# Connector.net
KiCad netlist of a schematic drawn in Altium Designer
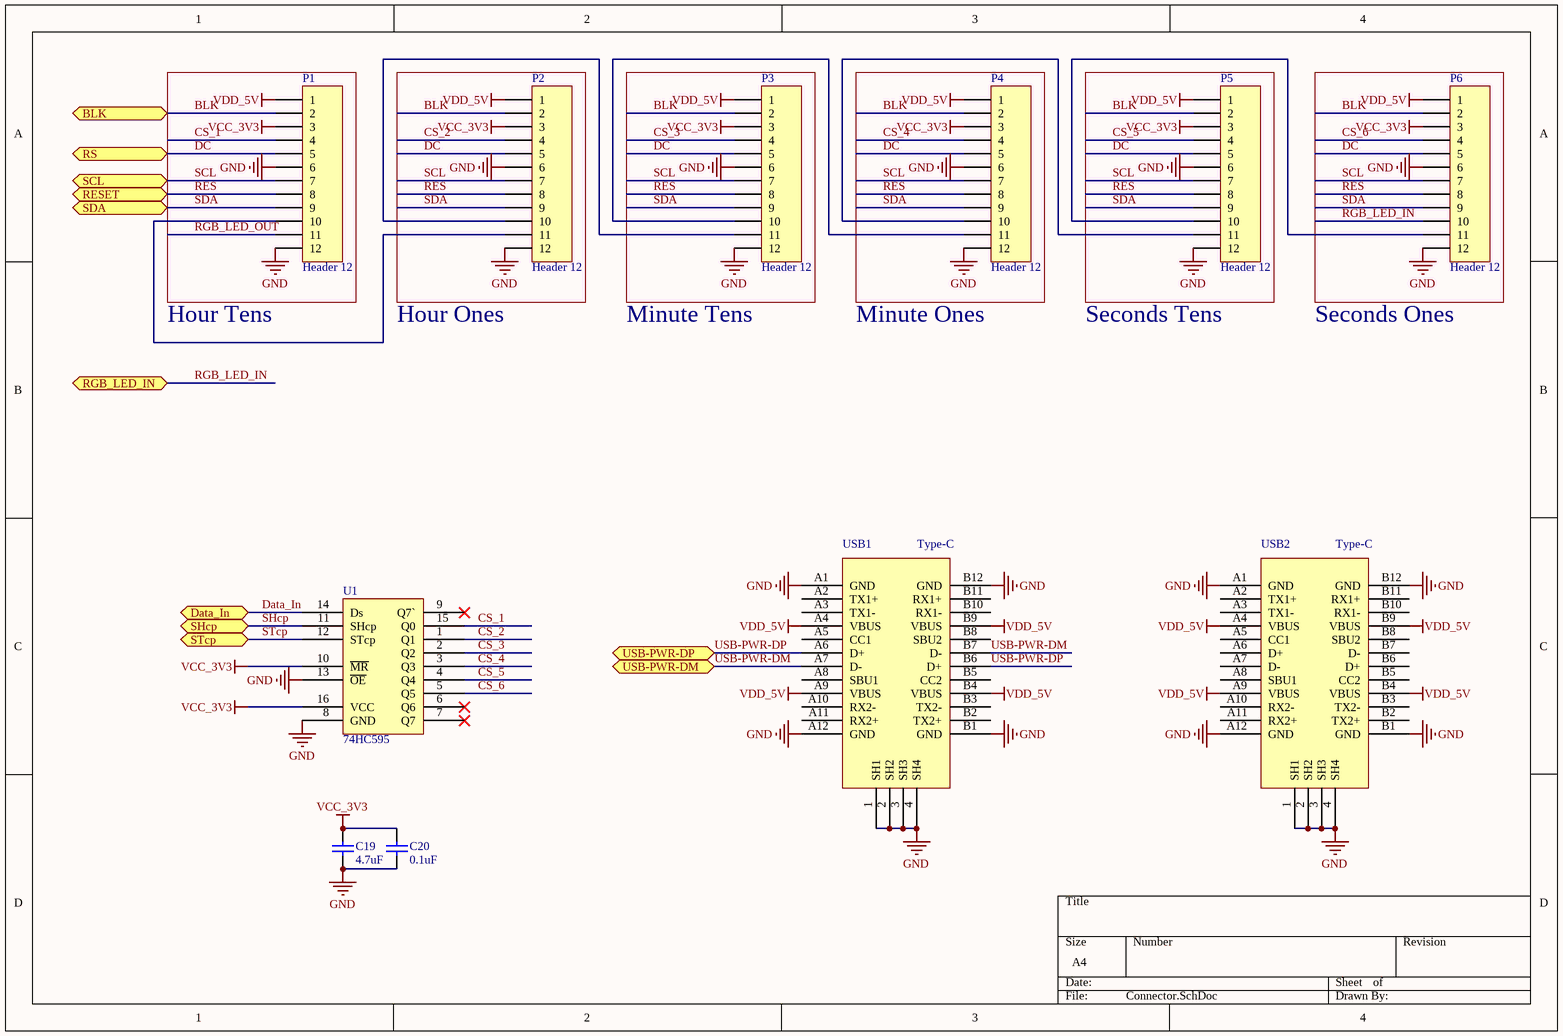
[diagram p0: Connector.SchDoc]

(export (version "E")
  (design (tool "Eeschema 10.0.6"))
  (components
    (comp (ref "C19")
      (value "4.7uF")
      (footprint "C0603")
      (description "Capacitor")
      (fields (field (name "PUBLISHER") "Altium Limited"))
      (libsource (lib "basic") (part "Cap"))
    )
    (comp (ref "C20")
      (value "0.1uF")
      (footprint "C0603")
      (description "Capacitor")
      (fields (field (name "PUBLISHER") "Altium Limited"))
      (libsource (lib "basic") (part "Cap"))
    )
    (comp (ref "P1")
      (value "Header 12")
      (footprint "SIP12-1.27")
      (description "Header, 12-Pin")
      (fields (field (name "PUBLISHER") "Altium Limited"))
      (libsource (lib "Miscellaneous Connectors") (part "Header 12"))
    )
    (comp (ref "P2")
      (value "Header 12")
      (footprint "SIP12-1.27")
      (description "Header, 12-Pin")
      (fields (field (name "PUBLISHER") "Altium Limited"))
      (libsource (lib "Miscellaneous Connectors") (part "Header 12"))
    )
    (comp (ref "P3")
      (value "Header 12")
      (footprint "SIP12-1.27")
      (description "Header, 12-Pin")
      (fields (field (name "PUBLISHER") "Altium Limited"))
      (libsource (lib "Miscellaneous Connectors") (part "Header 12"))
    )
    (comp (ref "P4")
      (value "Header 12")
      (footprint "SIP12-1.27")
      (description "Header, 12-Pin")
      (fields (field (name "PUBLISHER") "Altium Limited"))
      (libsource (lib "Miscellaneous Connectors") (part "Header 12"))
    )
    (comp (ref "P5")
      (value "Header 12")
      (footprint "SIP12-1.27")
      (description "Header, 12-Pin")
      (fields (field (name "PUBLISHER") "Altium Limited"))
      (libsource (lib "Miscellaneous Connectors") (part "Header 12"))
    )
    (comp (ref "P6")
      (value "Header 12")
      (footprint "SIP12-1.27")
      (description "Header, 12-Pin")
      (fields (field (name "PUBLISHER") "Altium Limited"))
      (libsource (lib "Miscellaneous Connectors") (part "Header 12"))
    )
    (comp (ref "U1")
      (value "74HC595")
      (footprint "SO-16_L")
      (libsource (lib "20210909_EleksTube_IPS") (part "74HC595"))
    )
    (comp (ref "USB1")
      (value "Type-C")
      (footprint "Type-C-TOP")
      (libsource (lib "MyPcbLib") (part "USB-Type-C-TOP"))
    )
    (comp (ref "USB2")
      (value "Type-C")
      (footprint "Type-C-TOP")
      (libsource (lib "MyPcbLib") (part "USB-Type-C-TOP"))
    )
  )
  (nets
    (net (code "1") (name "/BLK") (class "Default")
      (node (ref "P1") (pin "2") (pinfunction "2_2") (pintype "passive"))
      (node (ref "P2") (pin "2") (pinfunction "2_2") (pintype "passive"))
      (node (ref "P3") (pin "2") (pinfunction "2_2") (pintype "passive"))
      (node (ref "P4") (pin "2") (pinfunction "2_2") (pintype "passive"))
      (node (ref "P5") (pin "2") (pinfunction "2_2") (pintype "passive"))
      (node (ref "P6") (pin "2") (pinfunction "2_2") (pintype "passive"))
    )
    (net (code "2") (name "/CS_1") (class "Default")
      (node (ref "P1") (pin "4") (pinfunction "4_4") (pintype "passive"))
      (node (ref "U1") (pin "15") (pinfunction "Q0_15") (pintype "passive"))
    )
    (net (code "3") (name "/CS_2") (class "Default")
      (node (ref "P2") (pin "4") (pinfunction "4_4") (pintype "passive"))
      (node (ref "U1") (pin "1") (pinfunction "Q1_1") (pintype "passive"))
    )
    (net (code "4") (name "/CS_3") (class "Default")
      (node (ref "P3") (pin "4") (pinfunction "4_4") (pintype "passive"))
      (node (ref "U1") (pin "2") (pinfunction "Q2_2") (pintype "passive"))
    )
    (net (code "5") (name "/CS_4") (class "Default")
      (node (ref "P4") (pin "4") (pinfunction "4_4") (pintype "passive"))
      (node (ref "U1") (pin "3") (pinfunction "Q3_3") (pintype "passive"))
    )
    (net (code "6") (name "/CS_5") (class "Default")
      (node (ref "P5") (pin "4") (pinfunction "4_4") (pintype "passive"))
      (node (ref "U1") (pin "4") (pinfunction "Q4_4") (pintype "passive"))
    )
    (net (code "7") (name "/CS_6") (class "Default")
      (node (ref "P6") (pin "4") (pinfunction "4_4") (pintype "passive"))
      (node (ref "U1") (pin "5") (pinfunction "Q5_5") (pintype "passive"))
    )
    (net (code "8") (name "/DC") (class "Default")
      (node (ref "P1") (pin "5") (pinfunction "5_5") (pintype "passive"))
      (node (ref "P2") (pin "5") (pinfunction "5_5") (pintype "passive"))
      (node (ref "P3") (pin "5") (pinfunction "5_5") (pintype "passive"))
      (node (ref "P4") (pin "5") (pinfunction "5_5") (pintype "passive"))
      (node (ref "P5") (pin "5") (pinfunction "5_5") (pintype "passive"))
      (node (ref "P6") (pin "5") (pinfunction "5_5") (pintype "passive"))
    )
    (net (code "9") (name "/Data_In") (class "Default")
      (node (ref "U1") (pin "14") (pinfunction "Ds_14") (pintype "passive"))
    )
    (net (code "10") (name "/RES") (class "Default")
      (node (ref "P1") (pin "8") (pinfunction "8_8") (pintype "passive"))
      (node (ref "P2") (pin "8") (pinfunction "8_8") (pintype "passive"))
      (node (ref "P3") (pin "8") (pinfunction "8_8") (pintype "passive"))
      (node (ref "P4") (pin "8") (pinfunction "8_8") (pintype "passive"))
      (node (ref "P5") (pin "8") (pinfunction "8_8") (pintype "passive"))
      (node (ref "P6") (pin "8") (pinfunction "8_8") (pintype "passive"))
    )
    (net (code "11") (name "/RGB_LED_IN") (class "Default")
      (node (ref "P6") (pin "10") (pinfunction "10_10") (pintype "passive"))
    )
    (net (code "12") (name "/RGB_LED_OUT") (class "Default")
      (node (ref "P1") (pin "11") (pinfunction "11_11") (pintype "passive"))
    )
    (net (code "13") (name "/SCL") (class "Default")
      (node (ref "P1") (pin "7") (pinfunction "7_7") (pintype "passive"))
      (node (ref "P2") (pin "7") (pinfunction "7_7") (pintype "passive"))
      (node (ref "P3") (pin "7") (pinfunction "7_7") (pintype "passive"))
      (node (ref "P4") (pin "7") (pinfunction "7_7") (pintype "passive"))
      (node (ref "P5") (pin "7") (pinfunction "7_7") (pintype "passive"))
      (node (ref "P6") (pin "7") (pinfunction "7_7") (pintype "passive"))
    )
    (net (code "14") (name "/SDA") (class "Default")
      (node (ref "P1") (pin "9") (pinfunction "9_9") (pintype "passive"))
      (node (ref "P2") (pin "9") (pinfunction "9_9") (pintype "passive"))
      (node (ref "P3") (pin "9") (pinfunction "9_9") (pintype "passive"))
      (node (ref "P4") (pin "9") (pinfunction "9_9") (pintype "passive"))
      (node (ref "P5") (pin "9") (pinfunction "9_9") (pintype "passive"))
      (node (ref "P6") (pin "9") (pinfunction "9_9") (pintype "passive"))
    )
    (net (code "15") (name "/SHcp") (class "Default")
      (node (ref "U1") (pin "11") (pinfunction "SHcp_11") (pintype "passive"))
    )
    (net (code "16") (name "/STcp") (class "Default")
      (node (ref "U1") (pin "12") (pinfunction "STcp_12") (pintype "passive"))
    )
    (net (code "17") (name "/USB-PWR-DM") (class "Default")
      (node (ref "USB1") (pin "A7") (pinfunction "D-_A7") (pintype "passive"))
      (node (ref "USB1") (pin "B7") (pinfunction "D-_B7") (pintype "passive"))
    )
    (net (code "18") (name "/USB-PWR-DP") (class "Default")
      (node (ref "USB1") (pin "A6") (pinfunction "D+_A6") (pintype "passive"))
      (node (ref "USB1") (pin "B6") (pinfunction "D+_B6") (pintype "passive"))
    )
    (net (code "19") (name "GND") (class "Default")
      (node (ref "C19") (pin "2") (pinfunction "2_2") (pintype "passive"))
      (node (ref "C20") (pin "2") (pinfunction "2_2") (pintype "passive"))
      (node (ref "P1") (pin "12") (pinfunction "12_12") (pintype "passive"))
      (node (ref "P1") (pin "6") (pinfunction "6_6") (pintype "passive"))
      (node (ref "P2") (pin "12") (pinfunction "12_12") (pintype "passive"))
      (node (ref "P2") (pin "6") (pinfunction "6_6") (pintype "passive"))
      (node (ref "P3") (pin "12") (pinfunction "12_12") (pintype "passive"))
      (node (ref "P3") (pin "6") (pinfunction "6_6") (pintype "passive"))
      (node (ref "P4") (pin "12") (pinfunction "12_12") (pintype "passive"))
      (node (ref "P4") (pin "6") (pinfunction "6_6") (pintype "passive"))
      (node (ref "P5") (pin "12") (pinfunction "12_12") (pintype "passive"))
      (node (ref "P5") (pin "6") (pinfunction "6_6") (pintype "passive"))
      (node (ref "P6") (pin "12") (pinfunction "12_12") (pintype "passive"))
      (node (ref "P6") (pin "6") (pinfunction "6_6") (pintype "passive"))
      (node (ref "U1") (pin "13") (pinfunction "~{OE}_13") (pintype "passive"))
      (node (ref "U1") (pin "8") (pinfunction "GND_8") (pintype "passive"))
      (node (ref "USB1") (pin "1") (pinfunction "SH1_1") (pintype "passive"))
      (node (ref "USB1") (pin "2") (pinfunction "SH2_2") (pintype "passive"))
      (node (ref "USB1") (pin "3") (pinfunction "SH3_3") (pintype "passive"))
      (node (ref "USB1") (pin "4") (pinfunction "SH4_4") (pintype "passive"))
      (node (ref "USB1") (pin "A1") (pinfunction "GND_A1") (pintype "passive"))
      (node (ref "USB1") (pin "A12") (pinfunction "GND_A12") (pintype "passive"))
      (node (ref "USB1") (pin "B1") (pinfunction "GND_B1") (pintype "passive"))
      (node (ref "USB1") (pin "B12") (pinfunction "GND_B12") (pintype "passive"))
      (node (ref "USB2") (pin "1") (pinfunction "SH1_1") (pintype "passive"))
      (node (ref "USB2") (pin "2") (pinfunction "SH2_2") (pintype "passive"))
      (node (ref "USB2") (pin "3") (pinfunction "SH3_3") (pintype "passive"))
      (node (ref "USB2") (pin "4") (pinfunction "SH4_4") (pintype "passive"))
      (node (ref "USB2") (pin "A1") (pinfunction "GND_A1") (pintype "passive"))
      (node (ref "USB2") (pin "A12") (pinfunction "GND_A12") (pintype "passive"))
      (node (ref "USB2") (pin "B1") (pinfunction "GND_B1") (pintype "passive"))
      (node (ref "USB2") (pin "B12") (pinfunction "GND_B12") (pintype "passive"))
    )
    (net (code "20") (name "Net-(P1-Pad10)") (class "Default")
      (node (ref "P1") (pin "10") (pinfunction "10_10") (pintype "passive"))
      (node (ref "P2") (pin "11") (pinfunction "11_11") (pintype "passive"))
    )
    (net (code "21") (name "Net-(P2-Pad10)") (class "Default")
      (node (ref "P2") (pin "10") (pinfunction "10_10") (pintype "passive"))
      (node (ref "P3") (pin "11") (pinfunction "11_11") (pintype "passive"))
    )
    (net (code "22") (name "Net-(P3-Pad10)") (class "Default")
      (node (ref "P3") (pin "10") (pinfunction "10_10") (pintype "passive"))
      (node (ref "P4") (pin "11") (pinfunction "11_11") (pintype "passive"))
    )
    (net (code "23") (name "Net-(P4-Pad10)") (class "Default")
      (node (ref "P4") (pin "10") (pinfunction "10_10") (pintype "passive"))
      (node (ref "P5") (pin "11") (pinfunction "11_11") (pintype "passive"))
    )
    (net (code "24") (name "Net-(P5-Pad10)") (class "Default")
      (node (ref "P5") (pin "10") (pinfunction "10_10") (pintype "passive"))
      (node (ref "P6") (pin "11") (pinfunction "11_11") (pintype "passive"))
    )
    (net (code "25") (name "VCC_3V3") (class "Default")
      (node (ref "C19") (pin "1") (pinfunction "1_1") (pintype "passive"))
      (node (ref "C20") (pin "1") (pinfunction "1_1") (pintype "passive"))
      (node (ref "P1") (pin "3") (pinfunction "3_3") (pintype "passive"))
      (node (ref "P2") (pin "3") (pinfunction "3_3") (pintype "passive"))
      (node (ref "P3") (pin "3") (pinfunction "3_3") (pintype "passive"))
      (node (ref "P4") (pin "3") (pinfunction "3_3") (pintype "passive"))
      (node (ref "P5") (pin "3") (pinfunction "3_3") (pintype "passive"))
      (node (ref "P6") (pin "3") (pinfunction "3_3") (pintype "passive"))
      (node (ref "U1") (pin "10") (pinfunction "~{MR}_10") (pintype "passive"))
      (node (ref "U1") (pin "16") (pinfunction "VCC_16") (pintype "passive"))
    )
    (net (code "26") (name "VDD_5V") (class "Default")
      (node (ref "P1") (pin "1") (pinfunction "1_1") (pintype "passive"))
      (node (ref "P2") (pin "1") (pinfunction "1_1") (pintype "passive"))
      (node (ref "P3") (pin "1") (pinfunction "1_1") (pintype "passive"))
      (node (ref "P4") (pin "1") (pinfunction "1_1") (pintype "passive"))
      (node (ref "P5") (pin "1") (pinfunction "1_1") (pintype "passive"))
      (node (ref "P6") (pin "1") (pinfunction "1_1") (pintype "passive"))
      (node (ref "USB1") (pin "A4") (pinfunction "VBUS_A4") (pintype "passive"))
      (node (ref "USB1") (pin "A9") (pinfunction "VBUS_A9") (pintype "passive"))
      (node (ref "USB1") (pin "B4") (pinfunction "VBUS_B4") (pintype "passive"))
      (node (ref "USB1") (pin "B9") (pinfunction "VBUS_B9") (pintype "passive"))
      (node (ref "USB2") (pin "A4") (pinfunction "VBUS_A4") (pintype "passive"))
      (node (ref "USB2") (pin "A9") (pinfunction "VBUS_A9") (pintype "passive"))
      (node (ref "USB2") (pin "B4") (pinfunction "VBUS_B4") (pintype "passive"))
      (node (ref "USB2") (pin "B9") (pinfunction "VBUS_B9") (pintype "passive"))
    )
    (net (code "27") (name "unconnected-(U1-Q6-Pad6)") (class "Default")
      (node (ref "U1") (pin "6") (pinfunction "Q6_6") (pintype "passive+no_connect"))
    )
    (net (code "28") (name "unconnected-(U1-Q7-Pad7)") (class "Default")
      (node (ref "U1") (pin "7") (pinfunction "Q7_7") (pintype "passive+no_connect"))
    )
    (net (code "29") (name "unconnected-(U1-Q7`-Pad9)") (class "Default")
      (node (ref "U1") (pin "9") (pinfunction "Q7`_9") (pintype "passive+no_connect"))
    )
    (net (code "30") (name "unconnected-(USB1-CC1-PadA5)") (class "Default")
      (node (ref "USB1") (pin "A5") (pinfunction "CC1_A5") (pintype "passive"))
    )
    (net (code "31") (name "unconnected-(USB1-CC2-PadB5)") (class "Default")
      (node (ref "USB1") (pin "B5") (pinfunction "CC2_B5") (pintype "passive"))
    )
    (net (code "32") (name "unconnected-(USB1-RX1+-PadB11)") (class "Default")
      (node (ref "USB1") (pin "B11") (pinfunction "RX1+_B11") (pintype "passive"))
    )
    (net (code "33") (name "unconnected-(USB1-RX1--PadB10)") (class "Default")
      (node (ref "USB1") (pin "B10") (pinfunction "RX1-_B10") (pintype "passive"))
    )
    (net (code "34") (name "unconnected-(USB1-RX2+-PadA11)") (class "Default")
      (node (ref "USB1") (pin "A11") (pinfunction "RX2+_A11") (pintype "passive"))
    )
    (net (code "35") (name "unconnected-(USB1-RX2--PadA10)") (class "Default")
      (node (ref "USB1") (pin "A10") (pinfunction "RX2-_A10") (pintype "passive"))
    )
    (net (code "36") (name "unconnected-(USB1-SBU1-PadA8)") (class "Default")
      (node (ref "USB1") (pin "A8") (pinfunction "SBU1_A8") (pintype "passive"))
    )
    (net (code "37") (name "unconnected-(USB1-SBU2-PadB8)") (class "Default")
      (node (ref "USB1") (pin "B8") (pinfunction "SBU2_B8") (pintype "passive"))
    )
    (net (code "38") (name "unconnected-(USB1-TX1+-PadA2)") (class "Default")
      (node (ref "USB1") (pin "A2") (pinfunction "TX1+_A2") (pintype "passive"))
    )
    (net (code "39") (name "unconnected-(USB1-TX1--PadA3)") (class "Default")
      (node (ref "USB1") (pin "A3") (pinfunction "TX1-_A3") (pintype "passive"))
    )
    (net (code "40") (name "unconnected-(USB1-TX2+-PadB2)") (class "Default")
      (node (ref "USB1") (pin "B2") (pinfunction "TX2+_B2") (pintype "passive"))
    )
    (net (code "41") (name "unconnected-(USB1-TX2--PadB3)") (class "Default")
      (node (ref "USB1") (pin "B3") (pinfunction "TX2-_B3") (pintype "passive"))
    )
    (net (code "42") (name "unconnected-(USB2-CC1-PadA5)") (class "Default")
      (node (ref "USB2") (pin "A5") (pinfunction "CC1_A5") (pintype "passive"))
    )
    (net (code "43") (name "unconnected-(USB2-CC2-PadB5)") (class "Default")
      (node (ref "USB2") (pin "B5") (pinfunction "CC2_B5") (pintype "passive"))
    )
    (net (code "44") (name "unconnected-(USB2-D+-PadA6)") (class "Default")
      (node (ref "USB2") (pin "A6") (pinfunction "D+_A6") (pintype "passive"))
    )
    (net (code "45") (name "unconnected-(USB2-D+-PadB6)") (class "Default")
      (node (ref "USB2") (pin "B6") (pinfunction "D+_B6") (pintype "passive"))
    )
    (net (code "46") (name "unconnected-(USB2-D--PadA7)") (class "Default")
      (node (ref "USB2") (pin "A7") (pinfunction "D-_A7") (pintype "passive"))
    )
    (net (code "47") (name "unconnected-(USB2-D--PadB7)") (class "Default")
      (node (ref "USB2") (pin "B7") (pinfunction "D-_B7") (pintype "passive"))
    )
    (net (code "48") (name "unconnected-(USB2-RX1+-PadB11)") (class "Default")
      (node (ref "USB2") (pin "B11") (pinfunction "RX1+_B11") (pintype "passive"))
    )
    (net (code "49") (name "unconnected-(USB2-RX1--PadB10)") (class "Default")
      (node (ref "USB2") (pin "B10") (pinfunction "RX1-_B10") (pintype "passive"))
    )
    (net (code "50") (name "unconnected-(USB2-RX2+-PadA11)") (class "Default")
      (node (ref "USB2") (pin "A11") (pinfunction "RX2+_A11") (pintype "passive"))
    )
    (net (code "51") (name "unconnected-(USB2-RX2--PadA10)") (class "Default")
      (node (ref "USB2") (pin "A10") (pinfunction "RX2-_A10") (pintype "passive"))
    )
    (net (code "52") (name "unconnected-(USB2-SBU1-PadA8)") (class "Default")
      (node (ref "USB2") (pin "A8") (pinfunction "SBU1_A8") (pintype "passive"))
    )
    (net (code "53") (name "unconnected-(USB2-SBU2-PadB8)") (class "Default")
      (node (ref "USB2") (pin "B8") (pinfunction "SBU2_B8") (pintype "passive"))
    )
    (net (code "54") (name "unconnected-(USB2-TX1+-PadA2)") (class "Default")
      (node (ref "USB2") (pin "A2") (pinfunction "TX1+_A2") (pintype "passive"))
    )
    (net (code "55") (name "unconnected-(USB2-TX1--PadA3)") (class "Default")
      (node (ref "USB2") (pin "A3") (pinfunction "TX1-_A3") (pintype "passive"))
    )
    (net (code "56") (name "unconnected-(USB2-TX2+-PadB2)") (class "Default")
      (node (ref "USB2") (pin "B2") (pinfunction "TX2+_B2") (pintype "passive"))
    )
    (net (code "57") (name "unconnected-(USB2-TX2--PadB3)") (class "Default")
      (node (ref "USB2") (pin "B3") (pinfunction "TX2-_B3") (pintype "passive"))
    )
  )
)
